# Power.net
KiCad netlist of a schematic drawn in Altium Designer
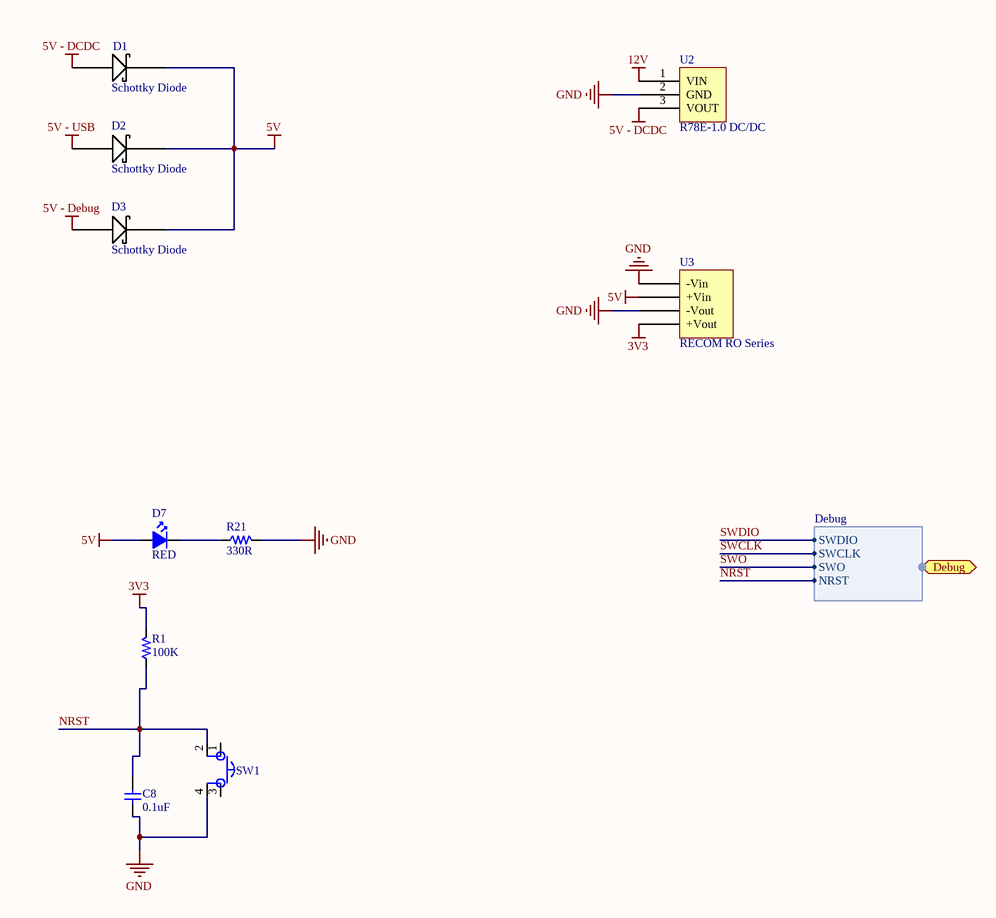
[diagram p0: Power.SchDoc]

(export (version "E")
  (design (tool "Eeschema 10.0.6"))
  (components
    (comp (ref "C8")
      (value "0.1uF")
      (footprint "PCB_GENERIC_SMD_0603")
      (description "CAP CER 0603 0.1uF 16V X5R 20%")
      (fields (field (name "TOLERANCE") "20%") (field (name "VOLTAGE") "16V"))
      (libsource (lib "CAP-0603") (part "C060-000U1-00"))
    )
    (comp (ref "D1")
      (value "Schottky Diode")
      (footprint "ON Semi Schottky Diode - MBRM110LT1G")
      (libsource (lib "ON Semi Schottky Diode - MBRM110LT1G") (part "ON Semi Schottky Diode - MBRM110LT1G"))
    )
    (comp (ref "D2")
      (value "Schottky Diode")
      (footprint "ON Semi Schottky Diode - MBRM110LT1G")
      (libsource (lib "ON Semi Schottky Diode - MBRM110LT1G") (part "ON Semi Schottky Diode - MBRM110LT1G"))
    )
    (comp (ref "D3")
      (value "Schottky Diode")
      (footprint "ON Semi Schottky Diode - MBRM110LT1G")
      (libsource (lib "ON Semi Schottky Diode - MBRM110LT1G") (part "ON Semi Schottky Diode - MBRM110LT1G"))
    )
    (comp (ref "D7")
      (value "D060-000R2-00")
      (footprint "SMD_0603_LED")
      (description "LED 0603 RED 2Vf 20mA")
      (fields (field (name "COLOR") "RED"))
      (libsource (lib "LED-0603") (part "D060-000R2-00"))
    )
    (comp (ref "R1")
      (value "100K")
      (footprint "PCB_GENERIC_SMD_0603")
      (description "RES 0603 100K 5% 63mW")
      (fields (field (name "TOLERANCE") "5%") (field (name "POWER") "63mW"))
      (libsource (lib "RES-0603") (part "R060-00104-05"))
    )
    (comp (ref "R21")
      (value "330R")
      (footprint "PCB_GENERIC_SMD_0603")
      (description "RES 0603 330ohm 5% 63mW")
      (fields (field (name "TOLERANCE") "5%") (field (name "POWER") "63mW"))
      (libsource (lib "RES-0603") (part "R060-00331-05"))
    )
    (comp (ref "SW1")
      (value "Tactile Switch")
      (footprint "C&K 4 pin Tactile Switch")
      (libsource (lib "C&K 4 Pin Tactile Switch") (part "C&K Tactile Switch"))
    )
    (comp (ref "U2")
      (value "R78E-1.0 DC/DC")
      (footprint "R78-1.0")
      (libsource (lib "R78E-1.0_DCDC_SCH") (part "R78E-1.0"))
    )
    (comp (ref "U3")
      (value "RECOM RO Series")
      (footprint "RECOM RO Series 1W DCDC")
      (libsource (lib "RECOM RO Series 1W DCDC") (part "RECOM RO Series DCDC Converter"))
    )
  )
  (nets
    (net (code "2") (name "/NRST") (class "Default")
      (node (ref "C8") (pin "2") (pinfunction "2_2") (pintype "passive"))
      (node (ref "R1") (pin "1") (pinfunction "1_1") (pintype "passive"))
      (node (ref "SW1") (pin "2") (pinfunction "2_2") (pintype "passive"))
    )
    (net (code "7") (name "3V3") (class "Default")
      (node (ref "R1") (pin "2") (pinfunction "2_2") (pintype "passive"))
      (node (ref "U3") (pin "4") (pinfunction "+Vout_4") (pintype "passive"))
    )
    (net (code "8") (name "5V") (class "Default")
      (node (ref "D1") (pin "1") (pinfunction "1_1") (pintype "passive"))
      (node (ref "D2") (pin "1") (pinfunction "1_1") (pintype "passive"))
      (node (ref "D3") (pin "1") (pinfunction "1_1") (pintype "passive"))
      (node (ref "D7") (pin "2") (pinfunction "A_2") (pintype "passive"))
      (node (ref "U3") (pin "2") (pinfunction "+Vin_2") (pintype "passive"))
    )
    (net (code "9") (name "5V - DCDC") (class "Default")
      (node (ref "D1") (pin "2") (pinfunction "2_2") (pintype "passive"))
      (node (ref "U2") (pin "3") (pinfunction "VOUT_3") (pintype "passive"))
    )
    (net (code "10") (name "5V - Debug") (class "Default")
      (node (ref "D3") (pin "2") (pinfunction "2_2") (pintype "passive"))
    )
    (net (code "11") (name "5V - USB") (class "Default")
      (node (ref "D2") (pin "2") (pinfunction "2_2") (pintype "passive"))
    )
    (net (code "12") (name "12V") (class "Default")
      (node (ref "U2") (pin "1") (pinfunction "VIN_1") (pintype "passive"))
    )
    (net (code "13") (name "GND") (class "Default")
      (node (ref "C8") (pin "1") (pinfunction "1_1") (pintype "passive"))
      (node (ref "R21") (pin "2") (pinfunction "2_2") (pintype "passive"))
      (node (ref "SW1") (pin "4") (pinfunction "4_4") (pintype "passive"))
      (node (ref "U2") (pin "2") (pinfunction "GND_2") (pintype "passive"))
      (node (ref "U3") (pin "1") (pinfunction "-Vin_1") (pintype "passive"))
      (node (ref "U3") (pin "3") (pinfunction "-Vout_3") (pintype "passive"))
    )
    (net (code "14") (name "Net-(D7-K)") (class "Default")
      (node (ref "D7") (pin "1") (pinfunction "K_1") (pintype "passive"))
      (node (ref "R21") (pin "1") (pinfunction "1_1") (pintype "passive"))
    )
    (net (code "15") (name "unconnected-(SW1-Pad1)") (class "Default")
      (node (ref "SW1") (pin "1") (pinfunction "1_1") (pintype "passive"))
    )
    (net (code "16") (name "unconnected-(SW1-Pad3)") (class "Default")
      (node (ref "SW1") (pin "3") (pinfunction "3_3") (pintype "passive"))
    )
  )
)
